# Sensorino-SMD.net
KiCad netlist of a schematic drawn in EAGLE
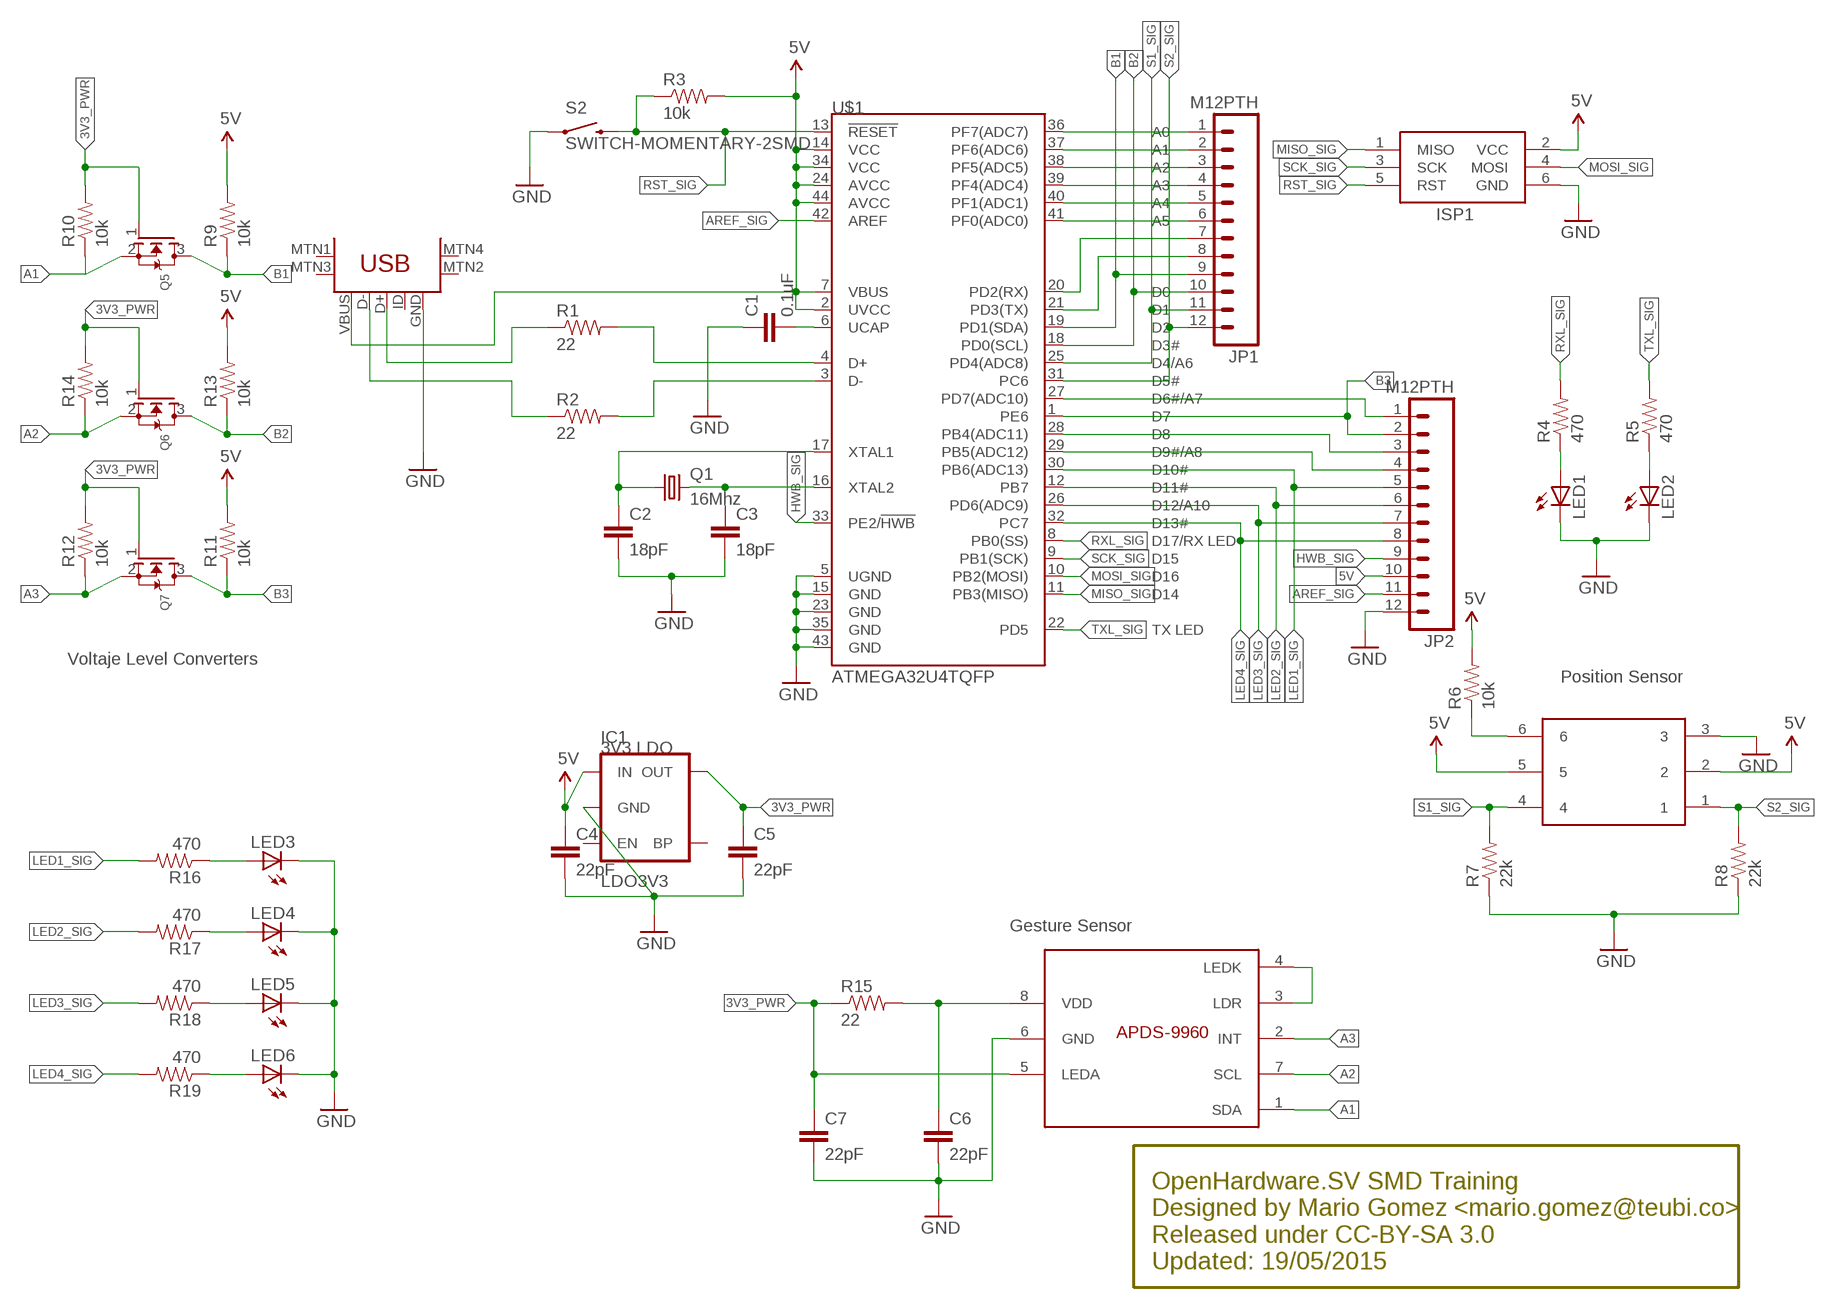
[diagram p0: schematic, sheet 1]

(export (version "E")
  (design (tool "Eeschema 10.0.6"))
  (components
    (comp (ref "C1")
      (value "0.1uF")
      (footprint "eagle-import:0805")
      (libsource (lib "eagle-import") (part "CAP0805"))
    )
    (comp (ref "C2")
      (value "18pF")
      (footprint "eagle-import:0805")
      (libsource (lib "eagle-import") (part "CAP0805"))
    )
    (comp (ref "C3")
      (value "18pF")
      (footprint "eagle-import:0805")
      (libsource (lib "eagle-import") (part "CAP0805"))
    )
    (comp (ref "C4")
      (value "22pF")
      (footprint "eagle-import:0805")
      (libsource (lib "eagle-import") (part "CAP0805"))
    )
    (comp (ref "C5")
      (value "22pF")
      (footprint "eagle-import:0805")
      (libsource (lib "eagle-import") (part "CAP0805"))
    )
    (comp (ref "C6")
      (value "22pF")
      (footprint "eagle-import:0805")
      (libsource (lib "eagle-import") (part "CAP0805"))
    )
    (comp (ref "C7")
      (value "22pF")
      (footprint "eagle-import:0805")
      (libsource (lib "eagle-import") (part "CAP0805"))
    )
    (comp (ref "IC1")
      (value "LDO3V3")
      (footprint "eagle-import:SOT23-5")
      (libsource (lib "eagle-import") (part "MIC52053.3V"))
    )
    (comp (ref "ISP1")
      (value "AVRISP-6")
      (footprint "eagle-import:AVRISP")
      (libsource (lib "eagle-import") (part "AVRISP-6"))
    )
    (comp (ref "JP1")
      (value "M12PTH")
      (footprint "eagle-import:1X12")
      (libsource (lib "eagle-import") (part "M12PTH"))
    )
    (comp (ref "JP2")
      (value "M12PTH")
      (footprint "eagle-import:1X12")
      (libsource (lib "eagle-import") (part "M12PTH"))
    )
    (comp (ref "LED1")
      (value "LED-WHITE")
      (footprint "eagle-import:LED-1206")
      (libsource (lib "eagle-import") (part "LED-WHITE"))
    )
    (comp (ref "LED2")
      (value "LED-WHITE")
      (footprint "eagle-import:LED-1206")
      (libsource (lib "eagle-import") (part "LED-WHITE"))
    )
    (comp (ref "LED3")
      (value "LED-WHITE")
      (footprint "eagle-import:LED-1206")
      (libsource (lib "eagle-import") (part "LED-WHITE"))
    )
    (comp (ref "LED4")
      (value "LED-WHITE")
      (footprint "eagle-import:LED-1206")
      (libsource (lib "eagle-import") (part "LED-WHITE"))
    )
    (comp (ref "LED5")
      (value "LED-WHITE")
      (footprint "eagle-import:LED-1206")
      (libsource (lib "eagle-import") (part "LED-WHITE"))
    )
    (comp (ref "LED6")
      (value "LED-WHITE")
      (footprint "eagle-import:LED-1206")
      (libsource (lib "eagle-import") (part "LED-WHITE"))
    )
    (comp (ref "Q1")
      (value "16Mhz")
      (footprint "eagle-import:CTS406")
      (libsource (lib "eagle-import") (part "CRYSTALCTS406"))
    )
    (comp (ref "Q5")
      (value "MOSFET-NREFLOW")
      (footprint "eagle-import:SOT23")
      (libsource (lib "eagle-import") (part "MOSFET-NREFLOW"))
    )
    (comp (ref "Q6")
      (value "MOSFET-NREFLOW")
      (footprint "eagle-import:SOT23")
      (libsource (lib "eagle-import") (part "MOSFET-NREFLOW"))
    )
    (comp (ref "Q7")
      (value "MOSFET-NREFLOW")
      (footprint "eagle-import:SOT23")
      (libsource (lib "eagle-import") (part "MOSFET-NREFLOW"))
    )
    (comp (ref "R1")
      (value "22")
      (footprint "eagle-import:0805")
      (libsource (lib "eagle-import") (part "RESISTOR0805-RES"))
    )
    (comp (ref "R2")
      (value "22")
      (footprint "eagle-import:0805")
      (libsource (lib "eagle-import") (part "RESISTOR0805-RES"))
    )
    (comp (ref "R3")
      (value "10k")
      (footprint "eagle-import:0805")
      (libsource (lib "eagle-import") (part "RESISTOR0805-RES"))
    )
    (comp (ref "R4")
      (value "470")
      (footprint "eagle-import:0805")
      (libsource (lib "eagle-import") (part "RESISTOR0805-RES"))
    )
    (comp (ref "R5")
      (value "470")
      (footprint "eagle-import:0805")
      (libsource (lib "eagle-import") (part "RESISTOR0805-RES"))
    )
    (comp (ref "R6")
      (value "10k")
      (footprint "eagle-import:0805")
      (libsource (lib "eagle-import") (part "RESISTOR0805-RES"))
    )
    (comp (ref "R7")
      (value "22k")
      (footprint "eagle-import:0805")
      (libsource (lib "eagle-import") (part "RESISTOR0805-RES"))
    )
    (comp (ref "R8")
      (value "22k")
      (footprint "eagle-import:0805")
      (libsource (lib "eagle-import") (part "RESISTOR0805-RES"))
    )
    (comp (ref "R9")
      (value "10k")
      (footprint "eagle-import:0805")
      (libsource (lib "eagle-import") (part "RESISTOR0805-RES"))
    )
    (comp (ref "R10")
      (value "10k")
      (footprint "eagle-import:0805")
      (libsource (lib "eagle-import") (part "RESISTOR0805-RES"))
    )
    (comp (ref "R11")
      (value "10k")
      (footprint "eagle-import:0805")
      (libsource (lib "eagle-import") (part "RESISTOR0805-RES"))
    )
    (comp (ref "R12")
      (value "10k")
      (footprint "eagle-import:0805")
      (libsource (lib "eagle-import") (part "RESISTOR0805-RES"))
    )
    (comp (ref "R13")
      (value "10k")
      (footprint "eagle-import:0805")
      (libsource (lib "eagle-import") (part "RESISTOR0805-RES"))
    )
    (comp (ref "R14")
      (value "10k")
      (footprint "eagle-import:0805")
      (libsource (lib "eagle-import") (part "RESISTOR0805-RES"))
    )
    (comp (ref "R15")
      (value "22")
      (footprint "eagle-import:0805")
      (libsource (lib "eagle-import") (part "RESISTOR0805-RES"))
    )
    (comp (ref "R16")
      (value "470")
      (footprint "eagle-import:0805")
      (libsource (lib "eagle-import") (part "RESISTOR0805-RES"))
    )
    (comp (ref "R17")
      (value "470")
      (footprint "eagle-import:0805")
      (libsource (lib "eagle-import") (part "RESISTOR0805-RES"))
    )
    (comp (ref "R18")
      (value "470")
      (footprint "eagle-import:0805")
      (libsource (lib "eagle-import") (part "RESISTOR0805-RES"))
    )
    (comp (ref "R19")
      (value "470")
      (footprint "eagle-import:0805")
      (libsource (lib "eagle-import") (part "RESISTOR0805-RES"))
    )
    (comp (ref "S2")
      (value "SWITCH-MOMENTARY-2SMD")
      (footprint "eagle-import:TACTILE_SWITCH_SMD")
      (libsource (lib "eagle-import") (part "SWITCH-MOMENTARY-2SMD"))
    )
    (comp (ref "U$1")
      (value "ATMEGA32U4TQFP")
      (footprint "eagle-import:SPARKFUN-DIGITALIC_TQFP44")
      (libsource (lib "eagle-import") (part "ATMEGA32U4TQFP"))
    )
    (comp (ref "U$2")
      (value "USB-MINIB-5PIN")
      (footprint "eagle-import:USB-MINIB")
      (libsource (lib "eagle-import") (part "USB-MINIB-5PIN"))
    )
    (comp (ref "U$3")
      (value "RPI-1031")
      (footprint "eagle-import:RPI-1031")
      (libsource (lib "eagle-import") (part "RPI-1031"))
    )
    (comp (ref "U$4")
      (value "APDS-9960")
      (footprint "eagle-import:APDS-9960")
      (libsource (lib "eagle-import") (part "APDS-9960"))
    )
  )
  (nets
    (net (code "1") (name "3V3_PWR") (class "Default")
      (node (ref "C5") (pin "1") (pinfunction "1_1") (pintype "passive"))
      (node (ref "C7") (pin "1") (pinfunction "1_1") (pintype "passive"))
      (node (ref "IC1") (pin "5") (pinfunction "OUT_5") (pintype "passive"))
      (node (ref "Q5") (pin "1") (pinfunction "G_1") (pintype "bidirectional"))
      (node (ref "Q6") (pin "1") (pinfunction "G_1") (pintype "bidirectional"))
      (node (ref "Q7") (pin "1") (pinfunction "G_1") (pintype "bidirectional"))
      (node (ref "R10") (pin "2") (pinfunction "2_2") (pintype "passive"))
      (node (ref "R12") (pin "2") (pinfunction "2_2") (pintype "passive"))
      (node (ref "R14") (pin "2") (pinfunction "2_2") (pintype "passive"))
      (node (ref "R15") (pin "1") (pinfunction "1_1") (pintype "passive"))
      (node (ref "U$4") (pin "5") (pinfunction "LEDA_5") (pintype "bidirectional"))
    )
    (net (code "2") (name "5V") (class "Default")
      (node (ref "C4") (pin "1") (pinfunction "1_1") (pintype "passive"))
      (node (ref "IC1") (pin "1") (pinfunction "IN_1") (pintype "input"))
      (node (ref "ISP1") (pin "2") (pinfunction "VCC_2") (pintype "power_in"))
      (node (ref "JP2") (pin "10") (pinfunction "10_10") (pintype "passive"))
      (node (ref "R11") (pin "2") (pinfunction "2_2") (pintype "passive"))
      (node (ref "R13") (pin "2") (pinfunction "2_2") (pintype "passive"))
      (node (ref "R3") (pin "2") (pinfunction "2_2") (pintype "passive"))
      (node (ref "R6") (pin "2") (pinfunction "2_2") (pintype "passive"))
      (node (ref "R9") (pin "2") (pinfunction "2_2") (pintype "passive"))
      (node (ref "U$1") (pin "14") (pinfunction "VCC_14") (pintype "bidirectional"))
      (node (ref "U$1") (pin "2") (pinfunction "UVCC_2") (pintype "bidirectional"))
      (node (ref "U$1") (pin "24") (pinfunction "AVCC_24") (pintype "bidirectional"))
      (node (ref "U$1") (pin "34") (pinfunction "VCC_34") (pintype "bidirectional"))
      (node (ref "U$1") (pin "44") (pinfunction "AVCC_44") (pintype "bidirectional"))
      (node (ref "U$1") (pin "7") (pinfunction "VBUS_7") (pintype "bidirectional"))
      (node (ref "U$2") (pin "VBUS") (pinfunction "VBUS_VBUS") (pintype "bidirectional"))
      (node (ref "U$3") (pin "2") (pinfunction "2_2") (pintype "bidirectional"))
      (node (ref "U$3") (pin "5") (pinfunction "5_5") (pintype "bidirectional"))
    )
    (net (code "3") (name "A1") (class "Default")
      (node (ref "Q5") (pin "2") (pinfunction "S_2") (pintype "bidirectional"))
      (node (ref "R10") (pin "1") (pinfunction "1_1") (pintype "passive"))
      (node (ref "U$4") (pin "1") (pinfunction "SDA_1") (pintype "bidirectional"))
    )
    (net (code "4") (name "A2") (class "Default")
      (node (ref "Q6") (pin "2") (pinfunction "S_2") (pintype "bidirectional"))
      (node (ref "R14") (pin "1") (pinfunction "1_1") (pintype "passive"))
      (node (ref "U$4") (pin "7") (pinfunction "SCL_7") (pintype "bidirectional"))
    )
    (net (code "5") (name "A3") (class "Default")
      (node (ref "Q7") (pin "2") (pinfunction "S_2") (pintype "bidirectional"))
      (node (ref "R12") (pin "1") (pinfunction "1_1") (pintype "passive"))
      (node (ref "U$4") (pin "2") (pinfunction "INT_2") (pintype "bidirectional"))
    )
    (net (code "6") (name "AREF_SIG") (class "Default")
      (node (ref "JP2") (pin "11") (pinfunction "11_11") (pintype "passive"))
      (node (ref "U$1") (pin "42") (pinfunction "AREF_42") (pintype "bidirectional"))
    )
    (net (code "7") (name "B1") (class "Default")
      (node (ref "JP1") (pin "9") (pinfunction "9_9") (pintype "passive"))
      (node (ref "Q5") (pin "3") (pinfunction "D_3") (pintype "bidirectional"))
      (node (ref "R9") (pin "1") (pinfunction "1_1") (pintype "passive"))
      (node (ref "U$1") (pin "19") (pinfunction "PD1(SDA)_19") (pintype "bidirectional"))
    )
    (net (code "8") (name "B2") (class "Default")
      (node (ref "JP1") (pin "10") (pinfunction "10_10") (pintype "passive"))
      (node (ref "Q6") (pin "3") (pinfunction "D_3") (pintype "bidirectional"))
      (node (ref "R13") (pin "1") (pinfunction "1_1") (pintype "passive"))
      (node (ref "U$1") (pin "18") (pinfunction "PD0(SCL)_18") (pintype "bidirectional"))
    )
    (net (code "9") (name "B3") (class "Default")
      (node (ref "JP2") (pin "2") (pinfunction "2_2") (pintype "passive"))
      (node (ref "Q7") (pin "3") (pinfunction "D_3") (pintype "bidirectional"))
      (node (ref "R11") (pin "1") (pinfunction "1_1") (pintype "passive"))
      (node (ref "U$1") (pin "1") (pinfunction "PE6_1") (pintype "bidirectional"))
    )
    (net (code "10") (name "GND") (class "Default")
      (node (ref "C1") (pin "1") (pinfunction "1_1") (pintype "passive"))
      (node (ref "C2") (pin "2") (pinfunction "2_2") (pintype "passive"))
      (node (ref "C3") (pin "2") (pinfunction "2_2") (pintype "passive"))
      (node (ref "C4") (pin "2") (pinfunction "2_2") (pintype "passive"))
      (node (ref "C5") (pin "2") (pinfunction "2_2") (pintype "passive"))
      (node (ref "C6") (pin "2") (pinfunction "2_2") (pintype "passive"))
      (node (ref "C7") (pin "2") (pinfunction "2_2") (pintype "passive"))
      (node (ref "IC1") (pin "2") (pinfunction "GND_2") (pintype "input"))
      (node (ref "ISP1") (pin "6") (pinfunction "GND_6") (pintype "power_in"))
      (node (ref "JP2") (pin "12") (pinfunction "12_12") (pintype "passive"))
      (node (ref "LED1") (pin "C") (pinfunction "C_C") (pintype "passive"))
      (node (ref "LED2") (pin "C") (pinfunction "C_C") (pintype "passive"))
      (node (ref "LED3") (pin "C") (pinfunction "C_C") (pintype "passive"))
      (node (ref "LED4") (pin "C") (pinfunction "C_C") (pintype "passive"))
      (node (ref "LED5") (pin "C") (pinfunction "C_C") (pintype "passive"))
      (node (ref "LED6") (pin "C") (pinfunction "C_C") (pintype "passive"))
      (node (ref "R7") (pin "1") (pinfunction "1_1") (pintype "passive"))
      (node (ref "R8") (pin "1") (pinfunction "1_1") (pintype "passive"))
      (node (ref "S2") (pin "1") (pinfunction "1_1") (pintype "passive"))
      (node (ref "U$1") (pin "15") (pinfunction "GND_15") (pintype "bidirectional"))
      (node (ref "U$1") (pin "23") (pinfunction "GND_23") (pintype "bidirectional"))
      (node (ref "U$1") (pin "35") (pinfunction "GND_35") (pintype "bidirectional"))
      (node (ref "U$1") (pin "43") (pinfunction "GND_43") (pintype "bidirectional"))
      (node (ref "U$1") (pin "5") (pinfunction "UGND_5") (pintype "bidirectional"))
      (node (ref "U$2") (pin "GND") (pinfunction "GND_GND") (pintype "bidirectional"))
      (node (ref "U$3") (pin "3") (pinfunction "3_3") (pintype "bidirectional"))
      (node (ref "U$4") (pin "6") (pinfunction "GND_6") (pintype "bidirectional"))
    )
    (net (code "11") (name "HWB_SIG") (class "Default")
      (node (ref "JP2") (pin "9") (pinfunction "9_9") (pintype "passive"))
      (node (ref "U$1") (pin "33") (pinfunction "PE2/~{HWB}_33") (pintype "bidirectional"))
    )
    (net (code "12") (name "LED1_SIG") (class "Default")
      (node (ref "JP2") (pin "5") (pinfunction "5_5") (pintype "passive"))
      (node (ref "R16") (pin "2") (pinfunction "2_2") (pintype "passive"))
      (node (ref "U$1") (pin "30") (pinfunction "PB6(ADC13)_30") (pintype "bidirectional"))
    )
    (net (code "13") (name "LED2_SIG") (class "Default")
      (node (ref "JP2") (pin "6") (pinfunction "6_6") (pintype "passive"))
      (node (ref "R17") (pin "2") (pinfunction "2_2") (pintype "passive"))
      (node (ref "U$1") (pin "12") (pinfunction "PB7_12") (pintype "bidirectional"))
    )
    (net (code "14") (name "LED3_SIG") (class "Default")
      (node (ref "JP2") (pin "7") (pinfunction "7_7") (pintype "passive"))
      (node (ref "R18") (pin "2") (pinfunction "2_2") (pintype "passive"))
      (node (ref "U$1") (pin "26") (pinfunction "PD6(ADC9)_26") (pintype "bidirectional"))
    )
    (net (code "15") (name "LED4_SIG") (class "Default")
      (node (ref "JP2") (pin "8") (pinfunction "8_8") (pintype "passive"))
      (node (ref "R19") (pin "2") (pinfunction "2_2") (pintype "passive"))
      (node (ref "U$1") (pin "32") (pinfunction "PC7_32") (pintype "bidirectional"))
    )
    (net (code "16") (name "MISO_SIG") (class "Default")
      (node (ref "ISP1") (pin "1") (pinfunction "MISO_1") (pintype "input"))
      (node (ref "U$1") (pin "11") (pinfunction "PB3(MISO)_11") (pintype "bidirectional"))
    )
    (net (code "17") (name "MOSI_SIG") (class "Default")
      (node (ref "ISP1") (pin "4") (pinfunction "MOSI_4") (pintype "output"))
      (node (ref "U$1") (pin "10") (pinfunction "PB2(MOSI)_10") (pintype "bidirectional"))
    )
    (net (code "18") (name "Net-(LED1-PadA)") (class "Default")
      (node (ref "LED1") (pin "A") (pinfunction "A_A") (pintype "passive"))
      (node (ref "R4") (pin "1") (pinfunction "1_1") (pintype "passive"))
    )
    (net (code "19") (name "Net-(LED2-PadA)") (class "Default")
      (node (ref "LED2") (pin "A") (pinfunction "A_A") (pintype "passive"))
      (node (ref "R5") (pin "1") (pinfunction "1_1") (pintype "passive"))
    )
    (net (code "20") (name "Net-(LED3-PadA)") (class "Default")
      (node (ref "LED3") (pin "A") (pinfunction "A_A") (pintype "passive"))
      (node (ref "R16") (pin "1") (pinfunction "1_1") (pintype "passive"))
    )
    (net (code "21") (name "Net-(LED4-PadA)") (class "Default")
      (node (ref "LED4") (pin "A") (pinfunction "A_A") (pintype "passive"))
      (node (ref "R17") (pin "1") (pinfunction "1_1") (pintype "passive"))
    )
    (net (code "22") (name "Net-(LED5-PadA)") (class "Default")
      (node (ref "LED5") (pin "A") (pinfunction "A_A") (pintype "passive"))
      (node (ref "R18") (pin "1") (pinfunction "1_1") (pintype "passive"))
    )
    (net (code "23") (name "Net-(LED6-PadA)") (class "Default")
      (node (ref "LED6") (pin "A") (pinfunction "A_A") (pintype "passive"))
      (node (ref "R19") (pin "1") (pinfunction "1_1") (pintype "passive"))
    )
    (net (code "24") (name "Net-(Q1-2)") (class "Default")
      (node (ref "C3") (pin "1") (pinfunction "1_1") (pintype "passive"))
      (node (ref "Q1") (pin "3") (pinfunction "2_3") (pintype "passive"))
      (node (ref "U$1") (pin "16") (pinfunction "XTAL2_16") (pintype "bidirectional"))
    )
    (net (code "25") (name "Net-(R1-Pad1)") (class "Default")
      (node (ref "R1") (pin "1") (pinfunction "1_1") (pintype "passive"))
      (node (ref "U$2") (pin "D+") (pinfunction "D+_D+") (pintype "bidirectional"))
    )
    (net (code "26") (name "Net-(R2-Pad1)") (class "Default")
      (node (ref "R2") (pin "1") (pinfunction "1_1") (pintype "passive"))
      (node (ref "U$2") (pin "D-") (pinfunction "D-_D-") (pintype "bidirectional"))
    )
    (net (code "27") (name "Net-(R6-Pad1)") (class "Default")
      (node (ref "R6") (pin "1") (pinfunction "1_1") (pintype "passive"))
      (node (ref "U$3") (pin "6") (pinfunction "6_6") (pintype "bidirectional"))
    )
    (net (code "28") (name "Net-(U$1-D+)") (class "Default")
      (node (ref "R1") (pin "2") (pinfunction "2_2") (pintype "passive"))
      (node (ref "U$1") (pin "4") (pinfunction "D+_4") (pintype "bidirectional"))
    )
    (net (code "29") (name "Net-(U$1-D-)") (class "Default")
      (node (ref "R2") (pin "2") (pinfunction "2_2") (pintype "passive"))
      (node (ref "U$1") (pin "3") (pinfunction "D-_3") (pintype "bidirectional"))
    )
    (net (code "30") (name "Net-(U$1-PB4(ADC11))") (class "Default")
      (node (ref "JP2") (pin "3") (pinfunction "3_3") (pintype "passive"))
      (node (ref "U$1") (pin "28") (pinfunction "PB4(ADC11)_28") (pintype "bidirectional"))
    )
    (net (code "31") (name "Net-(U$1-PB5(ADC12))") (class "Default")
      (node (ref "JP2") (pin "4") (pinfunction "4_4") (pintype "passive"))
      (node (ref "U$1") (pin "29") (pinfunction "PB5(ADC12)_29") (pintype "bidirectional"))
    )
    (net (code "32") (name "Net-(U$1-PD2(RX))") (class "Default")
      (node (ref "JP1") (pin "7") (pinfunction "7_7") (pintype "passive"))
      (node (ref "U$1") (pin "20") (pinfunction "PD2(RX)_20") (pintype "bidirectional"))
    )
    (net (code "33") (name "Net-(U$1-PD3(TX))") (class "Default")
      (node (ref "JP1") (pin "8") (pinfunction "8_8") (pintype "passive"))
      (node (ref "U$1") (pin "21") (pinfunction "PD3(TX)_21") (pintype "bidirectional"))
    )
    (net (code "34") (name "Net-(U$1-PD7(ADC10))") (class "Default")
      (node (ref "JP2") (pin "1") (pinfunction "1_1") (pintype "passive"))
      (node (ref "U$1") (pin "27") (pinfunction "PD7(ADC10)_27") (pintype "bidirectional"))
    )
    (net (code "35") (name "Net-(U$1-PF0(ADC0))") (class "Default")
      (node (ref "JP1") (pin "6") (pinfunction "6_6") (pintype "passive"))
      (node (ref "U$1") (pin "41") (pinfunction "PF0(ADC0)_41") (pintype "bidirectional"))
    )
    (net (code "36") (name "Net-(U$1-PF1(ADC1))") (class "Default")
      (node (ref "JP1") (pin "5") (pinfunction "5_5") (pintype "passive"))
      (node (ref "U$1") (pin "40") (pinfunction "PF1(ADC1)_40") (pintype "bidirectional"))
    )
    (net (code "37") (name "Net-(U$1-PF4(ADC4))") (class "Default")
      (node (ref "JP1") (pin "4") (pinfunction "4_4") (pintype "passive"))
      (node (ref "U$1") (pin "39") (pinfunction "PF4(ADC4)_39") (pintype "bidirectional"))
    )
    (net (code "38") (name "Net-(U$1-PF5(ADC5))") (class "Default")
      (node (ref "JP1") (pin "3") (pinfunction "3_3") (pintype "passive"))
      (node (ref "U$1") (pin "38") (pinfunction "PF5(ADC5)_38") (pintype "bidirectional"))
    )
    (net (code "39") (name "Net-(U$1-PF6(ADC6))") (class "Default")
      (node (ref "JP1") (pin "2") (pinfunction "2_2") (pintype "passive"))
      (node (ref "U$1") (pin "37") (pinfunction "PF6(ADC6)_37") (pintype "bidirectional"))
    )
    (net (code "40") (name "Net-(U$1-PF7(ADC7))") (class "Default")
      (node (ref "JP1") (pin "1") (pinfunction "1_1") (pintype "passive"))
      (node (ref "U$1") (pin "36") (pinfunction "PF7(ADC7)_36") (pintype "bidirectional"))
    )
    (net (code "41") (name "Net-(U$1-UCAP)") (class "Default")
      (node (ref "C1") (pin "2") (pinfunction "2_2") (pintype "passive"))
      (node (ref "U$1") (pin "6") (pinfunction "UCAP_6") (pintype "bidirectional"))
    )
    (net (code "42") (name "Net-(U$1-XTAL1)") (class "Default")
      (node (ref "C2") (pin "1") (pinfunction "1_1") (pintype "passive"))
      (node (ref "Q1") (pin "1") (pinfunction "1_1") (pintype "passive"))
      (node (ref "U$1") (pin "17") (pinfunction "XTAL1_17") (pintype "bidirectional"))
    )
    (net (code "43") (name "Net-(U$4-LDR)") (class "Default")
      (node (ref "U$4") (pin "3") (pinfunction "LDR_3") (pintype "bidirectional"))
      (node (ref "U$4") (pin "4") (pinfunction "LEDK_4") (pintype "bidirectional"))
    )
    (net (code "44") (name "Net-(U$4-VDD)") (class "Default")
      (node (ref "C6") (pin "1") (pinfunction "1_1") (pintype "passive"))
      (node (ref "R15") (pin "2") (pinfunction "2_2") (pintype "passive"))
      (node (ref "U$4") (pin "8") (pinfunction "VDD_8") (pintype "bidirectional"))
    )
    (net (code "45") (name "RST_SIG") (class "Default")
      (node (ref "ISP1") (pin "5") (pinfunction "RST_5") (pintype "output"))
      (node (ref "R3") (pin "1") (pinfunction "1_1") (pintype "passive"))
      (node (ref "S2") (pin "3") (pinfunction "2_3") (pintype "passive"))
      (node (ref "U$1") (pin "13") (pinfunction "~{RESET}_13") (pintype "bidirectional"))
    )
    (net (code "46") (name "RXL_SIG") (class "Default")
      (node (ref "R4") (pin "2") (pinfunction "2_2") (pintype "passive"))
      (node (ref "U$1") (pin "8") (pinfunction "PB0(SS)_8") (pintype "bidirectional"))
    )
    (net (code "47") (name "S1_SIG") (class "Default")
      (node (ref "JP1") (pin "11") (pinfunction "11_11") (pintype "passive"))
      (node (ref "R7") (pin "2") (pinfunction "2_2") (pintype "passive"))
      (node (ref "U$1") (pin "25") (pinfunction "PD4(ADC8)_25") (pintype "bidirectional"))
      (node (ref "U$3") (pin "4") (pinfunction "4_4") (pintype "bidirectional"))
    )
    (net (code "48") (name "S2_SIG") (class "Default")
      (node (ref "JP1") (pin "12") (pinfunction "12_12") (pintype "passive"))
      (node (ref "R8") (pin "2") (pinfunction "2_2") (pintype "passive"))
      (node (ref "U$1") (pin "31") (pinfunction "PC6_31") (pintype "bidirectional"))
      (node (ref "U$3") (pin "1") (pinfunction "1_1") (pintype "bidirectional"))
    )
    (net (code "49") (name "SCK_SIG") (class "Default")
      (node (ref "ISP1") (pin "3") (pinfunction "SCK_3") (pintype "output"))
      (node (ref "U$1") (pin "9") (pinfunction "PB1(SCK)_9") (pintype "bidirectional"))
    )
    (net (code "50") (name "TXL_SIG") (class "Default")
      (node (ref "R5") (pin "2") (pinfunction "2_2") (pintype "passive"))
      (node (ref "U$1") (pin "22") (pinfunction "PD5_22") (pintype "bidirectional"))
    )
    (net (code "51") (name "unconnected-(IC1-BP-Pad4)") (class "Default")
      (node (ref "IC1") (pin "4") (pinfunction "BP_4") (pintype "input"))
    )
    (net (code "52") (name "unconnected-(IC1-EN-Pad3)") (class "Default")
      (node (ref "IC1") (pin "3") (pinfunction "EN_3") (pintype "input"))
    )
    (net (code "53") (name "unconnected-(U$2-MTN1-PadMTN3)") (class "Default")
      (node (ref "U$2") (pin "MTN3") (pinfunction "MTN1_MTN3") (pintype "bidirectional"))
    )
    (net (code "54") (name "unconnected-(U$2-MTN2-PadMTN1)") (class "Default")
      (node (ref "U$2") (pin "MTN1") (pinfunction "MTN2_MTN1") (pintype "bidirectional"))
    )
    (net (code "55") (name "unconnected-(U$2-MTN3-PadMTN2)") (class "Default")
      (node (ref "U$2") (pin "MTN2") (pinfunction "MTN3_MTN2") (pintype "bidirectional"))
    )
    (net (code "56") (name "unconnected-(U$2-PadID)") (class "Default")
      (node (ref "U$2") (pin "ID") (pinfunction "ID_ID") (pintype "bidirectional"))
    )
    (net (code "57") (name "unconnected-(U$2-PadMTN4)") (class "Default")
      (node (ref "U$2") (pin "MTN4") (pinfunction "MTN4_MTN4") (pintype "bidirectional"))
    )
  )
)
